# H3_MIDIController_Rev_1_MainBoard.net
KiCad netlist of a schematic drawn in EAGLE
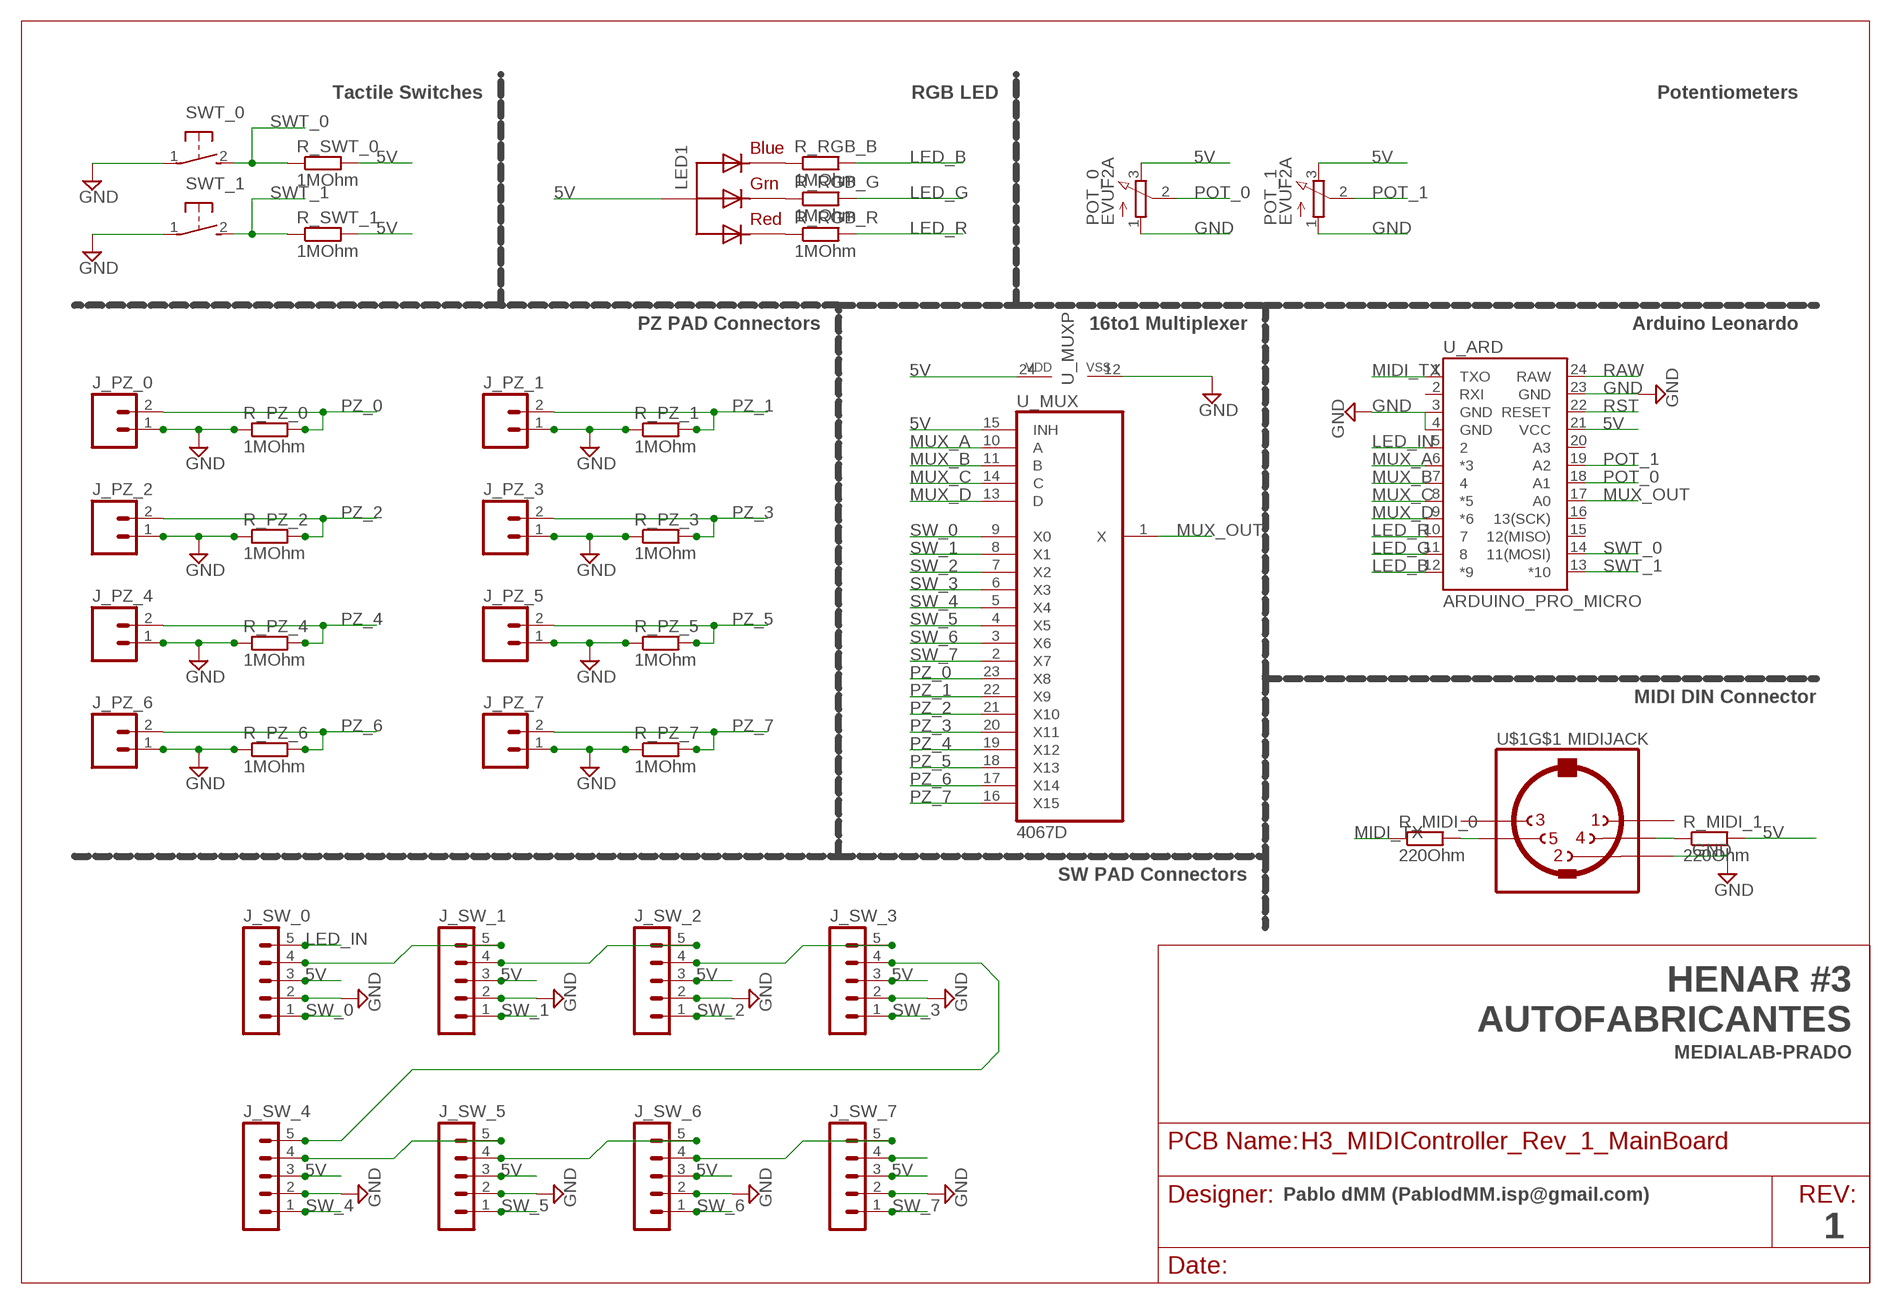
[diagram p0: schematic, sheet 1]

(export (version "E")
  (design (tool "Eeschema 10.0.6"))
  (components
    (comp (ref "J_PZ_0")
      (value "MA02")
      (footprint "eagle-import:02PA")
      (libsource (lib "eagle-import") (part "MA02"))
    )
    (comp (ref "J_PZ_1")
      (value "MA02")
      (footprint "eagle-import:02PA")
      (libsource (lib "eagle-import") (part "MA02"))
    )
    (comp (ref "J_PZ_2")
      (value "MA02")
      (footprint "eagle-import:02PA")
      (libsource (lib "eagle-import") (part "MA02"))
    )
    (comp (ref "J_PZ_3")
      (value "MA02")
      (footprint "eagle-import:02PA")
      (libsource (lib "eagle-import") (part "MA02"))
    )
    (comp (ref "J_PZ_4")
      (value "MA02")
      (footprint "eagle-import:02PA")
      (libsource (lib "eagle-import") (part "MA02"))
    )
    (comp (ref "J_PZ_5")
      (value "MA02")
      (footprint "eagle-import:02PA")
      (libsource (lib "eagle-import") (part "MA02"))
    )
    (comp (ref "J_PZ_6")
      (value "MA02")
      (footprint "eagle-import:02PA")
      (libsource (lib "eagle-import") (part "MA02"))
    )
    (comp (ref "J_PZ_7")
      (value "MA02")
      (footprint "eagle-import:02PA")
      (libsource (lib "eagle-import") (part "MA02"))
    )
    (comp (ref "J_SW_0")
      (value "MA05-1")
      (footprint "eagle-import:MA05-1")
      (libsource (lib "eagle-import") (part "MA05-1"))
    )
    (comp (ref "J_SW_1")
      (value "MA05-1")
      (footprint "eagle-import:MA05-1")
      (libsource (lib "eagle-import") (part "MA05-1"))
    )
    (comp (ref "J_SW_2")
      (value "MA05-1")
      (footprint "eagle-import:MA05-1")
      (libsource (lib "eagle-import") (part "MA05-1"))
    )
    (comp (ref "J_SW_3")
      (value "MA05-1")
      (footprint "eagle-import:MA05-1")
      (libsource (lib "eagle-import") (part "MA05-1"))
    )
    (comp (ref "J_SW_4")
      (value "MA05-1")
      (footprint "eagle-import:MA05-1")
      (libsource (lib "eagle-import") (part "MA05-1"))
    )
    (comp (ref "J_SW_5")
      (value "MA05-1")
      (footprint "eagle-import:MA05-1")
      (libsource (lib "eagle-import") (part "MA05-1"))
    )
    (comp (ref "J_SW_6")
      (value "MA05-1")
      (footprint "eagle-import:MA05-1")
      (libsource (lib "eagle-import") (part "MA05-1"))
    )
    (comp (ref "J_SW_7")
      (value "MA05-1")
      (footprint "eagle-import:MA05-1")
      (libsource (lib "eagle-import") (part "MA05-1"))
    )
    (comp (ref "LED1")
      (value "RGBLED_CA-5MM")
      (footprint "eagle-import:LED5MMRGB")
      (libsource (lib "eagle-import") (part "RGBLED_CA-5MM"))
    )
    (comp (ref "POT_0")
      (value "EVUF2A")
      (footprint "eagle-import:EVUF")
      (libsource (lib "eagle-import") (part "EVUAF2"))
    )
    (comp (ref "POT_1")
      (value "EVUF2A")
      (footprint "eagle-import:EVUF")
      (libsource (lib "eagle-import") (part "EVUAF2"))
    )
    (comp (ref "R_MIDI_0")
      (value "220Ohm")
      (footprint "eagle-import:M1206")
      (libsource (lib "eagle-import") (part "R-EU_M1206"))
    )
    (comp (ref "R_MIDI_1")
      (value "220Ohm")
      (footprint "eagle-import:M1206")
      (libsource (lib "eagle-import") (part "R-EU_M1206"))
    )
    (comp (ref "R_PZ_0")
      (value "1MOhm")
      (footprint "eagle-import:M1206")
      (libsource (lib "eagle-import") (part "R-EU_M1206"))
    )
    (comp (ref "R_PZ_1")
      (value "1MOhm")
      (footprint "eagle-import:M1206")
      (libsource (lib "eagle-import") (part "R-EU_M1206"))
    )
    (comp (ref "R_PZ_2")
      (value "1MOhm")
      (footprint "eagle-import:M1206")
      (libsource (lib "eagle-import") (part "R-EU_M1206"))
    )
    (comp (ref "R_PZ_3")
      (value "1MOhm")
      (footprint "eagle-import:M1206")
      (libsource (lib "eagle-import") (part "R-EU_M1206"))
    )
    (comp (ref "R_PZ_4")
      (value "1MOhm")
      (footprint "eagle-import:M1206")
      (libsource (lib "eagle-import") (part "R-EU_M1206"))
    )
    (comp (ref "R_PZ_5")
      (value "1MOhm")
      (footprint "eagle-import:M1206")
      (libsource (lib "eagle-import") (part "R-EU_M1206"))
    )
    (comp (ref "R_PZ_6")
      (value "1MOhm")
      (footprint "eagle-import:M1206")
      (libsource (lib "eagle-import") (part "R-EU_M1206"))
    )
    (comp (ref "R_PZ_7")
      (value "1MOhm")
      (footprint "eagle-import:M1206")
      (libsource (lib "eagle-import") (part "R-EU_M1206"))
    )
    (comp (ref "R_RGB_B")
      (value "1MOhm")
      (footprint "eagle-import:M1206")
      (libsource (lib "eagle-import") (part "R-EU_M1206"))
    )
    (comp (ref "R_RGB_G")
      (value "1MOhm")
      (footprint "eagle-import:M1206")
      (libsource (lib "eagle-import") (part "R-EU_M1206"))
    )
    (comp (ref "R_RGB_R")
      (value "1MOhm")
      (footprint "eagle-import:M1206")
      (libsource (lib "eagle-import") (part "R-EU_M1206"))
    )
    (comp (ref "R_SWT_0")
      (value "1MOhm")
      (footprint "eagle-import:M1206")
      (libsource (lib "eagle-import") (part "R-EU_M1206"))
    )
    (comp (ref "R_SWT_1")
      (value "1MOhm")
      (footprint "eagle-import:M1206")
      (libsource (lib "eagle-import") (part "R-EU_M1206"))
    )
    (comp (ref "SWT_0")
      (value "31-XX")
      (footprint "eagle-import:B3F-31XX")
      (fields (field (name "MPN") "B3F-3100"))
      (libsource (lib "eagle-import") (part "31-XX"))
    )
    (comp (ref "SWT_1")
      (value "31-XX")
      (footprint "eagle-import:B3F-31XX")
      (fields (field (name "MPN") "B3F-3100"))
      (libsource (lib "eagle-import") (part "31-XX"))
    )
    (comp (ref "U$1")
      (value "MIDIJACK")
      (footprint "eagle-import:CP-2350")
      (libsource (lib "eagle-import") (part "MIDIJACK"))
    )
    (comp (ref "U_ARD")
      (value "ARDUINO_PRO_MICRO")
      (footprint "eagle-import:ARDUINO_PRO_MICRO")
      (libsource (lib "eagle-import") (part "ARDUINO_PRO_MICRO"))
    )
    (comp (ref "U_MUX")
      (value "4067D")
      (footprint "eagle-import:SO24W")
      (libsource (lib "eagle-import") (part "4067D"))
    )
  )
  (nets
    (net (code "1") (name "/5V") (class "Default")
      (node (ref "J_SW_0") (pin "3") (pinfunction "3_3") (pintype "passive"))
      (node (ref "J_SW_1") (pin "3") (pinfunction "3_3") (pintype "passive"))
      (node (ref "J_SW_2") (pin "3") (pinfunction "3_3") (pintype "passive"))
      (node (ref "J_SW_3") (pin "3") (pinfunction "3_3") (pintype "passive"))
      (node (ref "J_SW_4") (pin "3") (pinfunction "3_3") (pintype "passive"))
      (node (ref "J_SW_5") (pin "3") (pinfunction "3_3") (pintype "passive"))
      (node (ref "J_SW_6") (pin "3") (pinfunction "3_3") (pintype "passive"))
      (node (ref "J_SW_7") (pin "3") (pinfunction "3_3") (pintype "passive"))
      (node (ref "LED1") (pin "2") (pinfunction "VCC_2") (pintype "bidirectional"))
      (node (ref "POT_0") (pin "3") (pinfunction "E_3") (pintype "passive"))
      (node (ref "POT_1") (pin "3") (pinfunction "E_3") (pintype "passive"))
      (node (ref "R_MIDI_1") (pin "2") (pinfunction "2_2") (pintype "passive"))
      (node (ref "R_SWT_0") (pin "2") (pinfunction "2_2") (pintype "passive"))
      (node (ref "R_SWT_1") (pin "2") (pinfunction "2_2") (pintype "passive"))
      (node (ref "U_ARD") (pin "21") (pinfunction "VCC_21") (pintype "bidirectional"))
      (node (ref "U_MUX") (pin "15") (pinfunction "INH_15") (pintype "input"))
      (node (ref "U_MUX") (pin "24") (pinfunction "VDD_24") (pintype "power_in"))
    )
    (net (code "2") (name "/LED_B") (class "Default")
      (node (ref "R_RGB_B") (pin "2") (pinfunction "2_2") (pintype "passive"))
      (node (ref "U_ARD") (pin "12") (pinfunction "*9_12") (pintype "bidirectional"))
    )
    (net (code "3") (name "/LED_G") (class "Default")
      (node (ref "R_RGB_G") (pin "2") (pinfunction "2_2") (pintype "passive"))
      (node (ref "U_ARD") (pin "11") (pinfunction "8_11") (pintype "bidirectional"))
    )
    (net (code "4") (name "/LED_IN") (class "Default")
      (node (ref "J_SW_0") (pin "5") (pinfunction "5_5") (pintype "passive"))
      (node (ref "U_ARD") (pin "5") (pinfunction "2_5") (pintype "bidirectional"))
    )
    (net (code "5") (name "/LED_R") (class "Default")
      (node (ref "R_RGB_R") (pin "2") (pinfunction "2_2") (pintype "passive"))
      (node (ref "U_ARD") (pin "10") (pinfunction "7_10") (pintype "bidirectional"))
    )
    (net (code "6") (name "/MIDI_TX") (class "Default")
      (node (ref "R_MIDI_0") (pin "1") (pinfunction "1_1") (pintype "passive"))
      (node (ref "U_ARD") (pin "1") (pinfunction "TXO_1") (pintype "bidirectional"))
    )
    (net (code "7") (name "/MUX_A") (class "Default")
      (node (ref "U_ARD") (pin "6") (pinfunction "*3_6") (pintype "bidirectional"))
      (node (ref "U_MUX") (pin "10") (pinfunction "A_10") (pintype "input"))
    )
    (net (code "8") (name "/MUX_B") (class "Default")
      (node (ref "U_ARD") (pin "7") (pinfunction "4_7") (pintype "bidirectional"))
      (node (ref "U_MUX") (pin "11") (pinfunction "B_11") (pintype "input"))
    )
    (net (code "9") (name "/MUX_C") (class "Default")
      (node (ref "U_ARD") (pin "8") (pinfunction "*5_8") (pintype "bidirectional"))
      (node (ref "U_MUX") (pin "14") (pinfunction "C_14") (pintype "input"))
    )
    (net (code "10") (name "/MUX_D") (class "Default")
      (node (ref "U_ARD") (pin "9") (pinfunction "*6_9") (pintype "bidirectional"))
      (node (ref "U_MUX") (pin "13") (pinfunction "D_13") (pintype "input"))
    )
    (net (code "11") (name "/MUX_OUT") (class "Default")
      (node (ref "U_ARD") (pin "17") (pinfunction "A0_17") (pintype "bidirectional"))
      (node (ref "U_MUX") (pin "1") (pinfunction "X_1") (pintype "output"))
    )
    (net (code "12") (name "/POT_0") (class "Default")
      (node (ref "POT_0") (pin "2") (pinfunction "S_2") (pintype "passive"))
      (node (ref "U_ARD") (pin "18") (pinfunction "A1_18") (pintype "bidirectional"))
    )
    (net (code "13") (name "/POT_1") (class "Default")
      (node (ref "POT_1") (pin "2") (pinfunction "S_2") (pintype "passive"))
      (node (ref "U_ARD") (pin "19") (pinfunction "A2_19") (pintype "bidirectional"))
    )
    (net (code "14") (name "/PZ_0") (class "Default")
      (node (ref "J_PZ_0") (pin "2") (pinfunction "2_2") (pintype "passive"))
      (node (ref "R_PZ_0") (pin "2") (pinfunction "2_2") (pintype "passive"))
      (node (ref "U_MUX") (pin "23") (pinfunction "X8_23") (pintype "input"))
    )
    (net (code "15") (name "/PZ_1") (class "Default")
      (node (ref "J_PZ_1") (pin "2") (pinfunction "2_2") (pintype "passive"))
      (node (ref "R_PZ_1") (pin "2") (pinfunction "2_2") (pintype "passive"))
      (node (ref "U_MUX") (pin "22") (pinfunction "X9_22") (pintype "input"))
    )
    (net (code "16") (name "/PZ_2") (class "Default")
      (node (ref "J_PZ_2") (pin "2") (pinfunction "2_2") (pintype "passive"))
      (node (ref "R_PZ_2") (pin "2") (pinfunction "2_2") (pintype "passive"))
      (node (ref "U_MUX") (pin "21") (pinfunction "X10_21") (pintype "input"))
    )
    (net (code "17") (name "/PZ_3") (class "Default")
      (node (ref "J_PZ_3") (pin "2") (pinfunction "2_2") (pintype "passive"))
      (node (ref "R_PZ_3") (pin "2") (pinfunction "2_2") (pintype "passive"))
      (node (ref "U_MUX") (pin "20") (pinfunction "X11_20") (pintype "input"))
    )
    (net (code "18") (name "/PZ_4") (class "Default")
      (node (ref "J_PZ_4") (pin "2") (pinfunction "2_2") (pintype "passive"))
      (node (ref "R_PZ_4") (pin "2") (pinfunction "2_2") (pintype "passive"))
      (node (ref "U_MUX") (pin "19") (pinfunction "X12_19") (pintype "input"))
    )
    (net (code "19") (name "/PZ_5") (class "Default")
      (node (ref "J_PZ_5") (pin "2") (pinfunction "2_2") (pintype "passive"))
      (node (ref "R_PZ_5") (pin "2") (pinfunction "2_2") (pintype "passive"))
      (node (ref "U_MUX") (pin "18") (pinfunction "X13_18") (pintype "input"))
    )
    (net (code "20") (name "/PZ_6") (class "Default")
      (node (ref "J_PZ_6") (pin "2") (pinfunction "2_2") (pintype "passive"))
      (node (ref "R_PZ_6") (pin "2") (pinfunction "2_2") (pintype "passive"))
      (node (ref "U_MUX") (pin "17") (pinfunction "X14_17") (pintype "input"))
    )
    (net (code "21") (name "/PZ_7") (class "Default")
      (node (ref "J_PZ_7") (pin "2") (pinfunction "2_2") (pintype "passive"))
      (node (ref "R_PZ_7") (pin "2") (pinfunction "2_2") (pintype "passive"))
      (node (ref "U_MUX") (pin "16") (pinfunction "X15_16") (pintype "input"))
    )
    (net (code "22") (name "/RAW") (class "Default")
      (node (ref "U_ARD") (pin "24") (pinfunction "RAW_24") (pintype "bidirectional"))
    )
    (net (code "23") (name "/RST") (class "Default")
      (node (ref "U_ARD") (pin "22") (pinfunction "RESET_22") (pintype "bidirectional"))
    )
    (net (code "24") (name "/SWT_0") (class "Default")
      (node (ref "R_SWT_0") (pin "1") (pinfunction "1_1") (pintype "passive"))
      (node (ref "SWT_0") (pin "2") (pinfunction "S_2") (pintype "passive"))
      (node (ref "U_ARD") (pin "14") (pinfunction "11(MOSI)_14") (pintype "bidirectional"))
    )
    (net (code "25") (name "/SWT_1") (class "Default")
      (node (ref "R_SWT_1") (pin "1") (pinfunction "1_1") (pintype "passive"))
      (node (ref "SWT_1") (pin "2") (pinfunction "S_2") (pintype "passive"))
      (node (ref "U_ARD") (pin "13") (pinfunction "*10_13") (pintype "bidirectional"))
    )
    (net (code "26") (name "/SW_0") (class "Default")
      (node (ref "J_SW_0") (pin "1") (pinfunction "1_1") (pintype "passive"))
      (node (ref "U_MUX") (pin "9") (pinfunction "X0_9") (pintype "input"))
    )
    (net (code "27") (name "/SW_1") (class "Default")
      (node (ref "J_SW_1") (pin "1") (pinfunction "1_1") (pintype "passive"))
      (node (ref "U_MUX") (pin "8") (pinfunction "X1_8") (pintype "input"))
    )
    (net (code "28") (name "/SW_2") (class "Default")
      (node (ref "J_SW_2") (pin "1") (pinfunction "1_1") (pintype "passive"))
      (node (ref "U_MUX") (pin "7") (pinfunction "X2_7") (pintype "input"))
    )
    (net (code "29") (name "/SW_3") (class "Default")
      (node (ref "J_SW_3") (pin "1") (pinfunction "1_1") (pintype "passive"))
      (node (ref "U_MUX") (pin "6") (pinfunction "X3_6") (pintype "input"))
    )
    (net (code "30") (name "/SW_4") (class "Default")
      (node (ref "J_SW_4") (pin "1") (pinfunction "1_1") (pintype "passive"))
      (node (ref "U_MUX") (pin "5") (pinfunction "X4_5") (pintype "input"))
    )
    (net (code "31") (name "/SW_5") (class "Default")
      (node (ref "J_SW_5") (pin "1") (pinfunction "1_1") (pintype "passive"))
      (node (ref "U_MUX") (pin "4") (pinfunction "X5_4") (pintype "input"))
    )
    (net (code "32") (name "/SW_6") (class "Default")
      (node (ref "J_SW_6") (pin "1") (pinfunction "1_1") (pintype "passive"))
      (node (ref "U_MUX") (pin "3") (pinfunction "X6_3") (pintype "input"))
    )
    (net (code "33") (name "/SW_7") (class "Default")
      (node (ref "J_SW_7") (pin "1") (pinfunction "1_1") (pintype "passive"))
      (node (ref "U_MUX") (pin "2") (pinfunction "X7_2") (pintype "input"))
    )
    (net (code "34") (name "GND") (class "Default")
      (node (ref "J_PZ_0") (pin "1") (pinfunction "1_1") (pintype "passive"))
      (node (ref "J_PZ_1") (pin "1") (pinfunction "1_1") (pintype "passive"))
      (node (ref "J_PZ_2") (pin "1") (pinfunction "1_1") (pintype "passive"))
      (node (ref "J_PZ_3") (pin "1") (pinfunction "1_1") (pintype "passive"))
      (node (ref "J_PZ_4") (pin "1") (pinfunction "1_1") (pintype "passive"))
      (node (ref "J_PZ_5") (pin "1") (pinfunction "1_1") (pintype "passive"))
      (node (ref "J_PZ_6") (pin "1") (pinfunction "1_1") (pintype "passive"))
      (node (ref "J_PZ_7") (pin "1") (pinfunction "1_1") (pintype "passive"))
      (node (ref "J_SW_0") (pin "2") (pinfunction "2_2") (pintype "passive"))
      (node (ref "J_SW_1") (pin "2") (pinfunction "2_2") (pintype "passive"))
      (node (ref "J_SW_2") (pin "2") (pinfunction "2_2") (pintype "passive"))
      (node (ref "J_SW_3") (pin "2") (pinfunction "2_2") (pintype "passive"))
      (node (ref "J_SW_4") (pin "2") (pinfunction "2_2") (pintype "passive"))
      (node (ref "J_SW_5") (pin "2") (pinfunction "2_2") (pintype "passive"))
      (node (ref "J_SW_6") (pin "2") (pinfunction "2_2") (pintype "passive"))
      (node (ref "J_SW_7") (pin "2") (pinfunction "2_2") (pintype "passive"))
      (node (ref "POT_0") (pin "1") (pinfunction "A_1") (pintype "passive"))
      (node (ref "POT_1") (pin "1") (pinfunction "A_1") (pintype "passive"))
      (node (ref "R_PZ_0") (pin "1") (pinfunction "1_1") (pintype "passive"))
      (node (ref "R_PZ_1") (pin "1") (pinfunction "1_1") (pintype "passive"))
      (node (ref "R_PZ_2") (pin "1") (pinfunction "1_1") (pintype "passive"))
      (node (ref "R_PZ_3") (pin "1") (pinfunction "1_1") (pintype "passive"))
      (node (ref "R_PZ_4") (pin "1") (pinfunction "1_1") (pintype "passive"))
      (node (ref "R_PZ_5") (pin "1") (pinfunction "1_1") (pintype "passive"))
      (node (ref "R_PZ_6") (pin "1") (pinfunction "1_1") (pintype "passive"))
      (node (ref "R_PZ_7") (pin "1") (pinfunction "1_1") (pintype "passive"))
      (node (ref "SWT_0") (pin "1") (pinfunction "P_1") (pintype "passive"))
      (node (ref "SWT_1") (pin "1") (pinfunction "P_1") (pintype "passive"))
      (node (ref "U$1") (pin "2") (pinfunction "2_2") (pintype "passive"))
      (node (ref "U_ARD") (pin "23") (pinfunction "GND_23") (pintype "bidirectional"))
      (node (ref "U_ARD") (pin "3") (pinfunction "GND_3") (pintype "bidirectional"))
      (node (ref "U_ARD") (pin "4") (pinfunction "GND_4") (pintype "bidirectional"))
      (node (ref "U_MUX") (pin "12") (pinfunction "VSS_12") (pintype "power_in"))
    )
    (net (code "35") (name "Net-(J_SW_0-Pad4)") (class "Default")
      (node (ref "J_SW_0") (pin "4") (pinfunction "4_4") (pintype "passive"))
      (node (ref "J_SW_1") (pin "5") (pinfunction "5_5") (pintype "passive"))
    )
    (net (code "36") (name "Net-(J_SW_1-Pad4)") (class "Default")
      (node (ref "J_SW_1") (pin "4") (pinfunction "4_4") (pintype "passive"))
      (node (ref "J_SW_2") (pin "5") (pinfunction "5_5") (pintype "passive"))
    )
    (net (code "37") (name "Net-(J_SW_2-Pad4)") (class "Default")
      (node (ref "J_SW_2") (pin "4") (pinfunction "4_4") (pintype "passive"))
      (node (ref "J_SW_3") (pin "5") (pinfunction "5_5") (pintype "passive"))
    )
    (net (code "38") (name "Net-(J_SW_3-Pad4)") (class "Default")
      (node (ref "J_SW_3") (pin "4") (pinfunction "4_4") (pintype "passive"))
      (node (ref "J_SW_4") (pin "5") (pinfunction "5_5") (pintype "passive"))
    )
    (net (code "39") (name "Net-(J_SW_4-Pad4)") (class "Default")
      (node (ref "J_SW_4") (pin "4") (pinfunction "4_4") (pintype "passive"))
      (node (ref "J_SW_5") (pin "5") (pinfunction "5_5") (pintype "passive"))
    )
    (net (code "40") (name "Net-(J_SW_5-Pad4)") (class "Default")
      (node (ref "J_SW_5") (pin "4") (pinfunction "4_4") (pintype "passive"))
      (node (ref "J_SW_6") (pin "5") (pinfunction "5_5") (pintype "passive"))
    )
    (net (code "41") (name "Net-(J_SW_6-Pad4)") (class "Default")
      (node (ref "J_SW_6") (pin "4") (pinfunction "4_4") (pintype "passive"))
      (node (ref "J_SW_7") (pin "5") (pinfunction "5_5") (pintype "passive"))
    )
    (net (code "42") (name "Net-(LED1-BLUE)") (class "Default")
      (node (ref "LED1") (pin "4") (pinfunction "BLUE_4") (pintype "bidirectional"))
      (node (ref "R_RGB_B") (pin "1") (pinfunction "1_1") (pintype "passive"))
    )
    (net (code "43") (name "Net-(LED1-GREEN)") (class "Default")
      (node (ref "LED1") (pin "3") (pinfunction "GREEN_3") (pintype "bidirectional"))
      (node (ref "R_RGB_G") (pin "1") (pinfunction "1_1") (pintype "passive"))
    )
    (net (code "44") (name "Net-(LED1-RED)") (class "Default")
      (node (ref "LED1") (pin "1") (pinfunction "RED_1") (pintype "bidirectional"))
      (node (ref "R_RGB_R") (pin "1") (pinfunction "1_1") (pintype "passive"))
    )
    (net (code "45") (name "Net-(R_MIDI_0-Pad2)") (class "Default")
      (node (ref "R_MIDI_0") (pin "2") (pinfunction "2_2") (pintype "passive"))
      (node (ref "U$1") (pin "5") (pinfunction "5_5") (pintype "passive"))
    )
    (net (code "46") (name "Net-(R_MIDI_1-Pad1)") (class "Default")
      (node (ref "R_MIDI_1") (pin "1") (pinfunction "1_1") (pintype "passive"))
      (node (ref "U$1") (pin "4") (pinfunction "4_4") (pintype "passive"))
    )
    (net (code "47") (name "unconnected-(J_SW_7-Pad4)") (class "Default")
      (node (ref "J_SW_7") (pin "4") (pinfunction "4_4") (pintype "passive"))
    )
    (net (code "48") (name "unconnected-(U$1-Pad1)") (class "Default")
      (node (ref "U$1") (pin "1") (pinfunction "1_1") (pintype "passive"))
    )
    (net (code "49") (name "unconnected-(U$1-Pad3)") (class "Default")
      (node (ref "U$1") (pin "3") (pinfunction "3_3") (pintype "passive"))
    )
    (net (code "50") (name "unconnected-(U_ARD-12(MISO)-Pad15)") (class "Default")
      (node (ref "U_ARD") (pin "15") (pinfunction "12(MISO)_15") (pintype "bidirectional"))
    )
    (net (code "51") (name "unconnected-(U_ARD-13(SCK)-Pad16)") (class "Default")
      (node (ref "U_ARD") (pin "16") (pinfunction "13(SCK)_16") (pintype "bidirectional"))
    )
    (net (code "52") (name "unconnected-(U_ARD-A3-Pad20)") (class "Default")
      (node (ref "U_ARD") (pin "20") (pinfunction "A3_20") (pintype "bidirectional"))
    )
    (net (code "53") (name "unconnected-(U_ARD-RXI-Pad2)") (class "Default")
      (node (ref "U_ARD") (pin "2") (pinfunction "RXI_2") (pintype "bidirectional"))
    )
  )
)
